# Electrical_Schematic_EasyEDA.net
KiCad netlist of a schematic drawn in EasyEDA
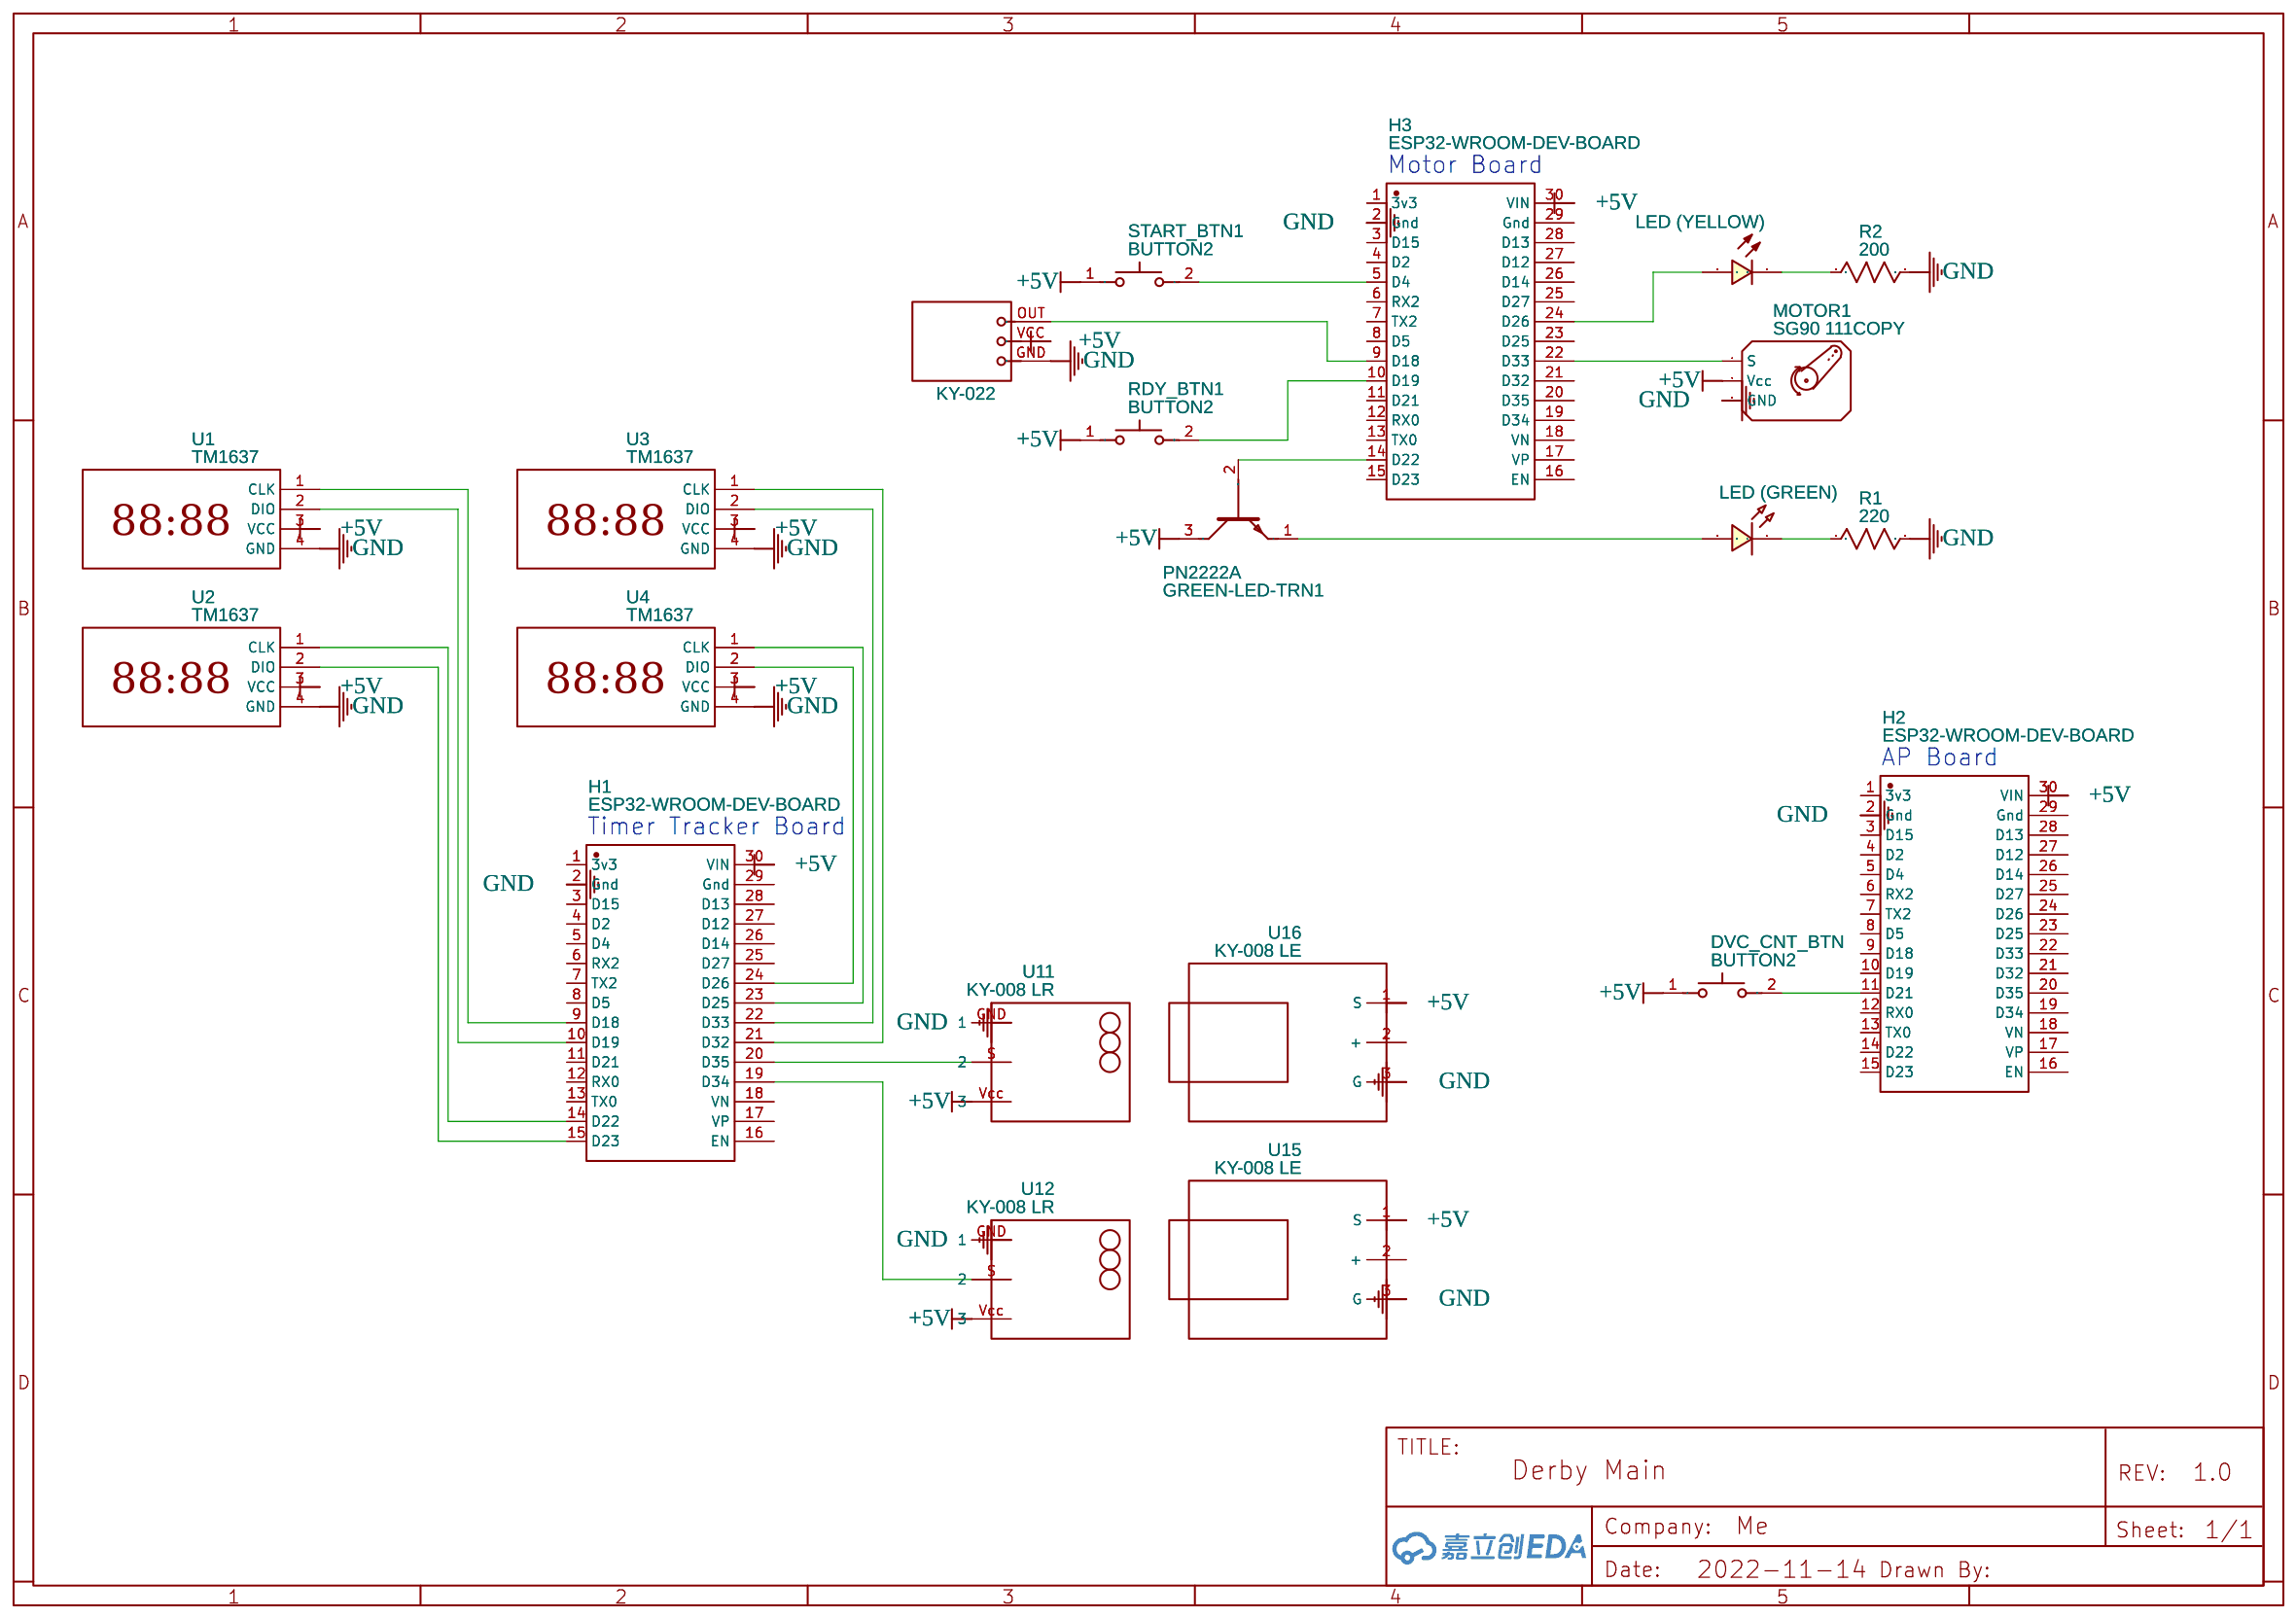
[diagram p0: schematic sheet]

(export (version "E")
  (design (tool "Eeschema 10.0.6"))
  (components
    (comp (ref "DVC_CNT_BTN")
      (value "BUTTON2")
      (fields (field (name "BOM_Supplier Part") "C9900005988"))
      (libsource (lib "") (part "BUTTON2_2"))
    )
    (comp (ref "GREEN-LED-TRN1") (value "PN2222A") (libsource (lib "") (part "PN2222A")))
    (comp (ref "H1")
      (value "ESP32-WROOM-DEV-BOARD")
      (fields
        (field (name "BOM_Manufacturer Part") "ESP32-WROOM-DEV")
        (field (name "BOM_Supplier Part") "ESP32")
      )
      (libsource (lib "") (part "ESP32-WROOM-DEV-BOARD"))
    )
    (comp (ref "H2")
      (value "ESP32-WROOM-DEV-BOARD")
      (fields
        (field (name "BOM_Manufacturer Part") "ESP32-WROOM-DEV")
        (field (name "BOM_Supplier Part") "ESP32")
      )
      (libsource (lib "") (part "ESP32-WROOM-DEV-BOARD"))
    )
    (comp (ref "H3")
      (value "ESP32-WROOM-DEV-BOARD")
      (fields
        (field (name "BOM_Manufacturer Part") "ESP32-WROOM-DEV")
        (field (name "BOM_Supplier Part") "ESP32")
      )
      (libsource (lib "") (part "ESP32-WROOM-DEV-BOARD"))
    )
    (comp (ref "LED1")
      (value "LED (GREEN)")
      (fields
        (field (name "BOM_Manufacturer Part") "LED三色(Red,Yellow,Green)")
        (field (name "BOM_Supplier Part") "C9900027004")
      )
      (libsource (lib "") (part "LED (GREEN)"))
    )
    (comp (ref "LED2")
      (value "LED (YELLOW)")
      (fields
        (field (name "BOM_Manufacturer Part") "19-213/Y2C-CQ1R1L/3T")
        (field (name "BOM_Supplier Part") "C264455")
      )
      (libsource (lib "") (part "Yellow LED"))
    )
    (comp (ref "MOTOR1") (value "SG90 111COPY") (libsource (lib "") (part "SG90 111COPY")))
    (comp (ref "R1") (value "220") (libsource (lib "") (part "R_AXIAL-0.6_US")))
    (comp (ref "R2") (value "200") (libsource (lib "") (part "R_AXIAL-0.6_US")))
    (comp (ref "RDY_BTN1")
      (value "BUTTON2")
      (fields (field (name "BOM_Supplier Part") "C9900005988"))
      (libsource (lib "") (part "BUTTON2"))
    )
    (comp (ref "START_BTN1")
      (value "BUTTON2")
      (fields (field (name "BOM_Supplier Part") "C9900005988"))
      (libsource (lib "") (part "BUTTON2_1"))
    )
    (comp (ref "U1") (value "TM1637") (libsource (lib "") (part "TM1637")))
    (comp (ref "U2") (value "TM1637") (libsource (lib "") (part "TM1637")))
    (comp (ref "U3") (value "TM1637") (libsource (lib "") (part "TM1637")))
    (comp (ref "U4") (value "TM1637") (libsource (lib "") (part "TM1637")))
    (comp (ref "U5") (value "KY-022") (libsource (lib "") (part "KY-022")))
    (comp (ref "U11")
      (value "KY-008 LR")
      (fields (field (name "BOM_Supplier Part") "KY-008"))
      (libsource (lib "") (part "Laser Receiver (KY-008)"))
    )
    (comp (ref "U12")
      (value "KY-008 LR")
      (fields (field (name "BOM_Supplier Part") "KY-008"))
      (libsource (lib "") (part "Laser Receiver (KY-008)"))
    )
    (comp (ref "U15") (value "KY-008 LE") (libsource (lib "") (part "KY-008//")))
    (comp (ref "U16") (value "KY-008 LE") (libsource (lib "") (part "KY-008//")))
  )
  (nets
    (net (code "1") (name "+5V") (class "Default")
      (node (ref "DVC_CNT_BTN") (pin "1") (pinfunction "1_1") (pintype "unspecified"))
      (node (ref "GREEN-LED-TRN1") (pin "3") (pinfunction "C_3") (pintype "bidirectional"))
      (node (ref "H1") (pin "30") (pinfunction "VIN_30") (pintype "unspecified"))
      (node (ref "H2") (pin "30") (pinfunction "VIN_30") (pintype "unspecified"))
      (node (ref "H3") (pin "30") (pinfunction "VIN_30") (pintype "unspecified"))
      (node (ref "MOTOR1") (pin "2") (pinfunction "Vcc_2") (pintype "unspecified"))
      (node (ref "RDY_BTN1") (pin "1") (pinfunction "1_1") (pintype "unspecified"))
      (node (ref "START_BTN1") (pin "1") (pinfunction "1_1") (pintype "unspecified"))
      (node (ref "U1") (pin "3") (pinfunction "VCC_3") (pintype "unspecified"))
      (node (ref "U15") (pin "1") (pinfunction "S_1") (pintype "unspecified"))
      (node (ref "U16") (pin "1") (pinfunction "S_1") (pintype "unspecified"))
      (node (ref "U2") (pin "3") (pinfunction "VCC_3") (pintype "unspecified"))
      (node (ref "U3") (pin "3") (pinfunction "VCC_3") (pintype "unspecified"))
      (node (ref "U4") (pin "3") (pinfunction "VCC_3") (pintype "unspecified"))
      (node (ref "U5") (pin "VCC") (pinfunction "2_VCC") (pintype "unspecified"))
    )
    (net (code "2") (name "GND") (class "Default")
      (node (ref "H1") (pin "2") (pinfunction "Gnd_2") (pintype "unspecified"))
      (node (ref "H2") (pin "2") (pinfunction "Gnd_2") (pintype "unspecified"))
      (node (ref "H3") (pin "2") (pinfunction "Gnd_2") (pintype "unspecified"))
      (node (ref "MOTOR1") (pin "3") (pinfunction "GND_3") (pintype "unspecified"))
      (node (ref "R1") (pin "2") (pinfunction "2_2") (pintype "unspecified"))
      (node (ref "R2") (pin "2") (pinfunction "2_2") (pintype "unspecified"))
      (node (ref "U1") (pin "4") (pinfunction "GND_4") (pintype "unspecified"))
      (node (ref "U11") (pin "GND") (pinfunction "1_GND") (pintype "unspecified"))
      (node (ref "U12") (pin "GND") (pinfunction "1_GND") (pintype "unspecified"))
      (node (ref "U15") (pin "3") (pinfunction "G_3") (pintype "unspecified"))
      (node (ref "U16") (pin "3") (pinfunction "G_3") (pintype "unspecified"))
      (node (ref "U2") (pin "4") (pinfunction "GND_4") (pintype "unspecified"))
      (node (ref "U3") (pin "4") (pinfunction "GND_4") (pintype "unspecified"))
      (node (ref "U4") (pin "4") (pinfunction "GND_4") (pintype "unspecified"))
      (node (ref "U5") (pin "GND") (pinfunction "1_GND") (pintype "unspecified"))
    )
    (net (code "3") (name "Net-(GREEN-LED-TRN1-B)") (class "Default")
      (node (ref "GREEN-LED-TRN1") (pin "2") (pinfunction "B_2") (pintype "bidirectional"))
      (node (ref "H3") (pin "14") (pinfunction "D22_14") (pintype "unspecified"))
    )
    (net (code "4") (name "Net-(GREEN-LED-TRN1-E)") (class "Default")
      (node (ref "GREEN-LED-TRN1") (pin "1") (pinfunction "E_1") (pintype "bidirectional"))
      (node (ref "LED1") (pin "2") (pinfunction "2_2") (pintype "unspecified"))
    )
    (net (code "5") (name "Net-(H1-D18)") (class "Default")
      (node (ref "H1") (pin "9") (pinfunction "D18_9") (pintype "unspecified"))
      (node (ref "U1") (pin "1") (pinfunction "CLK_1") (pintype "unspecified"))
    )
    (net (code "6") (name "Net-(H1-D19)") (class "Default")
      (node (ref "H1") (pin "10") (pinfunction "D19_10") (pintype "unspecified"))
      (node (ref "U1") (pin "2") (pinfunction "DIO_2") (pintype "unspecified"))
    )
    (net (code "7") (name "Net-(H1-D22)") (class "Default")
      (node (ref "H1") (pin "14") (pinfunction "D22_14") (pintype "unspecified"))
      (node (ref "U2") (pin "1") (pinfunction "CLK_1") (pintype "unspecified"))
    )
    (net (code "8") (name "Net-(H1-D23)") (class "Default")
      (node (ref "H1") (pin "15") (pinfunction "D23_15") (pintype "unspecified"))
      (node (ref "U2") (pin "2") (pinfunction "DIO_2") (pintype "unspecified"))
    )
    (net (code "9") (name "Net-(H1-D25)") (class "Default")
      (node (ref "H1") (pin "23") (pinfunction "D25_23") (pintype "unspecified"))
      (node (ref "U4") (pin "1") (pinfunction "CLK_1") (pintype "unspecified"))
    )
    (net (code "10") (name "Net-(H1-D26)") (class "Default")
      (node (ref "H1") (pin "24") (pinfunction "D26_24") (pintype "unspecified"))
      (node (ref "U4") (pin "2") (pinfunction "DIO_2") (pintype "unspecified"))
    )
    (net (code "11") (name "Net-(H1-D32)") (class "Default")
      (node (ref "H1") (pin "21") (pinfunction "D32_21") (pintype "unspecified"))
      (node (ref "U3") (pin "1") (pinfunction "CLK_1") (pintype "unspecified"))
    )
    (net (code "12") (name "Net-(H1-D33)") (class "Default")
      (node (ref "H1") (pin "22") (pinfunction "D33_22") (pintype "unspecified"))
      (node (ref "U3") (pin "2") (pinfunction "DIO_2") (pintype "unspecified"))
    )
    (net (code "13") (name "Net-(H1-D34)") (class "Default")
      (node (ref "H1") (pin "19") (pinfunction "D34_19") (pintype "unspecified"))
      (node (ref "U12") (pin "S") (pinfunction "2_S") (pintype "unspecified"))
    )
    (net (code "14") (name "Net-(H1-D35)") (class "Default")
      (node (ref "H1") (pin "20") (pinfunction "D35_20") (pintype "unspecified"))
      (node (ref "U11") (pin "S") (pinfunction "2_S") (pintype "unspecified"))
    )
    (net (code "15") (name "Net-(H2-D21)") (class "Default")
      (node (ref "DVC_CNT_BTN") (pin "2") (pinfunction "2_2") (pintype "unspecified"))
      (node (ref "H2") (pin "11") (pinfunction "D21_11") (pintype "unspecified"))
    )
    (net (code "16") (name "Net-(H3-D4)") (class "Default")
      (node (ref "H3") (pin "5") (pinfunction "D4_5") (pintype "unspecified"))
      (node (ref "START_BTN1") (pin "2") (pinfunction "2_2") (pintype "unspecified"))
    )
    (net (code "17") (name "Net-(H3-D18)") (class "Default")
      (node (ref "H3") (pin "9") (pinfunction "D18_9") (pintype "unspecified"))
      (node (ref "U5") (pin "OUT") (pinfunction "3_OUT") (pintype "unspecified"))
    )
    (net (code "18") (name "Net-(H3-D19)") (class "Default")
      (node (ref "H3") (pin "10") (pinfunction "D19_10") (pintype "unspecified"))
      (node (ref "RDY_BTN1") (pin "2") (pinfunction "2_2") (pintype "unspecified"))
    )
    (net (code "19") (name "Net-(H3-D26)") (class "Default")
      (node (ref "H3") (pin "24") (pinfunction "D26_24") (pintype "unspecified"))
      (node (ref "LED2") (pin "2") (pinfunction "A_2") (pintype "input"))
    )
    (net (code "20") (name "Net-(H3-D33)") (class "Default")
      (node (ref "H3") (pin "22") (pinfunction "D33_22") (pintype "unspecified"))
      (node (ref "MOTOR1") (pin "1") (pinfunction "S_1") (pintype "unspecified"))
    )
    (net (code "21") (name "Net-(LED1-Pad1)") (class "Default")
      (node (ref "LED1") (pin "1") (pinfunction "1_1") (pintype "unspecified"))
      (node (ref "R1") (pin "1") (pinfunction "1_1") (pintype "unspecified"))
    )
    (net (code "22") (name "Net-(LED2-C)") (class "Default")
      (node (ref "LED2") (pin "1") (pinfunction "C_1") (pintype "input"))
      (node (ref "R2") (pin "1") (pinfunction "1_1") (pintype "unspecified"))
    )
    (net (code "23") (name "unconnected-(H1-3v3-Pad1)") (class "Default")
      (node (ref "H1") (pin "1") (pinfunction "3v3_1") (pintype "unspecified"))
    )
    (net (code "24") (name "unconnected-(H1-D2-Pad4)") (class "Default")
      (node (ref "H1") (pin "4") (pinfunction "D2_4") (pintype "unspecified"))
    )
    (net (code "25") (name "unconnected-(H1-D4-Pad5)") (class "Default")
      (node (ref "H1") (pin "5") (pinfunction "D4_5") (pintype "unspecified"))
    )
    (net (code "26") (name "unconnected-(H1-D5-Pad8)") (class "Default")
      (node (ref "H1") (pin "8") (pinfunction "D5_8") (pintype "unspecified"))
    )
    (net (code "27") (name "unconnected-(H1-D12-Pad27)") (class "Default")
      (node (ref "H1") (pin "27") (pinfunction "D12_27") (pintype "unspecified"))
    )
    (net (code "28") (name "unconnected-(H1-D13-Pad28)") (class "Default")
      (node (ref "H1") (pin "28") (pinfunction "D13_28") (pintype "unspecified"))
    )
    (net (code "29") (name "unconnected-(H1-D14-Pad26)") (class "Default")
      (node (ref "H1") (pin "26") (pinfunction "D14_26") (pintype "unspecified"))
    )
    (net (code "30") (name "unconnected-(H1-D15-Pad3)") (class "Default")
      (node (ref "H1") (pin "3") (pinfunction "D15_3") (pintype "unspecified"))
    )
    (net (code "31") (name "unconnected-(H1-D21-Pad11)") (class "Default")
      (node (ref "H1") (pin "11") (pinfunction "D21_11") (pintype "unspecified"))
    )
    (net (code "32") (name "unconnected-(H1-D27-Pad25)") (class "Default")
      (node (ref "H1") (pin "25") (pinfunction "D27_25") (pintype "unspecified"))
    )
    (net (code "33") (name "unconnected-(H1-EN-Pad16)") (class "Default")
      (node (ref "H1") (pin "16") (pinfunction "EN_16") (pintype "unspecified"))
    )
    (net (code "34") (name "unconnected-(H1-Gnd-Pad29)") (class "Default")
      (node (ref "H1") (pin "29") (pinfunction "Gnd_29") (pintype "unspecified"))
    )
    (net (code "35") (name "unconnected-(H1-RX0-Pad12)") (class "Default")
      (node (ref "H1") (pin "12") (pinfunction "RX0_12") (pintype "unspecified"))
    )
    (net (code "36") (name "unconnected-(H1-RX2-Pad6)") (class "Default")
      (node (ref "H1") (pin "6") (pinfunction "RX2_6") (pintype "unspecified"))
    )
    (net (code "37") (name "unconnected-(H1-TX0-Pad13)") (class "Default")
      (node (ref "H1") (pin "13") (pinfunction "TX0_13") (pintype "unspecified"))
    )
    (net (code "38") (name "unconnected-(H1-TX2-Pad7)") (class "Default")
      (node (ref "H1") (pin "7") (pinfunction "TX2_7") (pintype "unspecified"))
    )
    (net (code "39") (name "unconnected-(H1-VN-Pad18)") (class "Default")
      (node (ref "H1") (pin "18") (pinfunction "VN_18") (pintype "unspecified"))
    )
    (net (code "40") (name "unconnected-(H1-VP-Pad17)") (class "Default")
      (node (ref "H1") (pin "17") (pinfunction "VP_17") (pintype "unspecified"))
    )
    (net (code "41") (name "unconnected-(H2-3v3-Pad1)") (class "Default")
      (node (ref "H2") (pin "1") (pinfunction "3v3_1") (pintype "unspecified"))
    )
    (net (code "42") (name "unconnected-(H2-D2-Pad4)") (class "Default")
      (node (ref "H2") (pin "4") (pinfunction "D2_4") (pintype "unspecified"))
    )
    (net (code "43") (name "unconnected-(H2-D4-Pad5)") (class "Default")
      (node (ref "H2") (pin "5") (pinfunction "D4_5") (pintype "unspecified"))
    )
    (net (code "44") (name "unconnected-(H2-D5-Pad8)") (class "Default")
      (node (ref "H2") (pin "8") (pinfunction "D5_8") (pintype "unspecified"))
    )
    (net (code "45") (name "unconnected-(H2-D12-Pad27)") (class "Default")
      (node (ref "H2") (pin "27") (pinfunction "D12_27") (pintype "unspecified"))
    )
    (net (code "46") (name "unconnected-(H2-D13-Pad28)") (class "Default")
      (node (ref "H2") (pin "28") (pinfunction "D13_28") (pintype "unspecified"))
    )
    (net (code "47") (name "unconnected-(H2-D14-Pad26)") (class "Default")
      (node (ref "H2") (pin "26") (pinfunction "D14_26") (pintype "unspecified"))
    )
    (net (code "48") (name "unconnected-(H2-D15-Pad3)") (class "Default")
      (node (ref "H2") (pin "3") (pinfunction "D15_3") (pintype "unspecified"))
    )
    (net (code "49") (name "unconnected-(H2-D18-Pad9)") (class "Default")
      (node (ref "H2") (pin "9") (pinfunction "D18_9") (pintype "unspecified"))
    )
    (net (code "50") (name "unconnected-(H2-D19-Pad10)") (class "Default")
      (node (ref "H2") (pin "10") (pinfunction "D19_10") (pintype "unspecified"))
    )
    (net (code "51") (name "unconnected-(H2-D22-Pad14)") (class "Default")
      (node (ref "H2") (pin "14") (pinfunction "D22_14") (pintype "unspecified"))
    )
    (net (code "52") (name "unconnected-(H2-D23-Pad15)") (class "Default")
      (node (ref "H2") (pin "15") (pinfunction "D23_15") (pintype "unspecified"))
    )
    (net (code "53") (name "unconnected-(H2-D25-Pad23)") (class "Default")
      (node (ref "H2") (pin "23") (pinfunction "D25_23") (pintype "unspecified"))
    )
    (net (code "54") (name "unconnected-(H2-D26-Pad24)") (class "Default")
      (node (ref "H2") (pin "24") (pinfunction "D26_24") (pintype "unspecified"))
    )
    (net (code "55") (name "unconnected-(H2-D27-Pad25)") (class "Default")
      (node (ref "H2") (pin "25") (pinfunction "D27_25") (pintype "unspecified"))
    )
    (net (code "56") (name "unconnected-(H2-D32-Pad21)") (class "Default")
      (node (ref "H2") (pin "21") (pinfunction "D32_21") (pintype "unspecified"))
    )
    (net (code "57") (name "unconnected-(H2-D33-Pad22)") (class "Default")
      (node (ref "H2") (pin "22") (pinfunction "D33_22") (pintype "unspecified"))
    )
    (net (code "58") (name "unconnected-(H2-D34-Pad19)") (class "Default")
      (node (ref "H2") (pin "19") (pinfunction "D34_19") (pintype "unspecified"))
    )
    (net (code "59") (name "unconnected-(H2-D35-Pad20)") (class "Default")
      (node (ref "H2") (pin "20") (pinfunction "D35_20") (pintype "unspecified"))
    )
    (net (code "60") (name "unconnected-(H2-EN-Pad16)") (class "Default")
      (node (ref "H2") (pin "16") (pinfunction "EN_16") (pintype "unspecified"))
    )
    (net (code "61") (name "unconnected-(H2-Gnd-Pad29)") (class "Default")
      (node (ref "H2") (pin "29") (pinfunction "Gnd_29") (pintype "unspecified"))
    )
    (net (code "62") (name "unconnected-(H2-RX0-Pad12)") (class "Default")
      (node (ref "H2") (pin "12") (pinfunction "RX0_12") (pintype "unspecified"))
    )
    (net (code "63") (name "unconnected-(H2-RX2-Pad6)") (class "Default")
      (node (ref "H2") (pin "6") (pinfunction "RX2_6") (pintype "unspecified"))
    )
    (net (code "64") (name "unconnected-(H2-TX0-Pad13)") (class "Default")
      (node (ref "H2") (pin "13") (pinfunction "TX0_13") (pintype "unspecified"))
    )
    (net (code "65") (name "unconnected-(H2-TX2-Pad7)") (class "Default")
      (node (ref "H2") (pin "7") (pinfunction "TX2_7") (pintype "unspecified"))
    )
    (net (code "66") (name "unconnected-(H2-VN-Pad18)") (class "Default")
      (node (ref "H2") (pin "18") (pinfunction "VN_18") (pintype "unspecified"))
    )
    (net (code "67") (name "unconnected-(H2-VP-Pad17)") (class "Default")
      (node (ref "H2") (pin "17") (pinfunction "VP_17") (pintype "unspecified"))
    )
    (net (code "68") (name "unconnected-(H3-3v3-Pad1)") (class "Default")
      (node (ref "H3") (pin "1") (pinfunction "3v3_1") (pintype "unspecified"))
    )
    (net (code "69") (name "unconnected-(H3-D2-Pad4)") (class "Default")
      (node (ref "H3") (pin "4") (pinfunction "D2_4") (pintype "unspecified"))
    )
    (net (code "70") (name "unconnected-(H3-D5-Pad8)") (class "Default")
      (node (ref "H3") (pin "8") (pinfunction "D5_8") (pintype "unspecified"))
    )
    (net (code "71") (name "unconnected-(H3-D12-Pad27)") (class "Default")
      (node (ref "H3") (pin "27") (pinfunction "D12_27") (pintype "unspecified"))
    )
    (net (code "72") (name "unconnected-(H3-D13-Pad28)") (class "Default")
      (node (ref "H3") (pin "28") (pinfunction "D13_28") (pintype "unspecified"))
    )
    (net (code "73") (name "unconnected-(H3-D14-Pad26)") (class "Default")
      (node (ref "H3") (pin "26") (pinfunction "D14_26") (pintype "unspecified"))
    )
    (net (code "74") (name "unconnected-(H3-D15-Pad3)") (class "Default")
      (node (ref "H3") (pin "3") (pinfunction "D15_3") (pintype "unspecified"))
    )
    (net (code "75") (name "unconnected-(H3-D21-Pad11)") (class "Default")
      (node (ref "H3") (pin "11") (pinfunction "D21_11") (pintype "unspecified"))
    )
    (net (code "76") (name "unconnected-(H3-D23-Pad15)") (class "Default")
      (node (ref "H3") (pin "15") (pinfunction "D23_15") (pintype "unspecified"))
    )
    (net (code "77") (name "unconnected-(H3-D25-Pad23)") (class "Default")
      (node (ref "H3") (pin "23") (pinfunction "D25_23") (pintype "unspecified"))
    )
    (net (code "78") (name "unconnected-(H3-D27-Pad25)") (class "Default")
      (node (ref "H3") (pin "25") (pinfunction "D27_25") (pintype "unspecified"))
    )
    (net (code "79") (name "unconnected-(H3-D32-Pad21)") (class "Default")
      (node (ref "H3") (pin "21") (pinfunction "D32_21") (pintype "unspecified"))
    )
    (net (code "80") (name "unconnected-(H3-D34-Pad19)") (class "Default")
      (node (ref "H3") (pin "19") (pinfunction "D34_19") (pintype "unspecified"))
    )
    (net (code "81") (name "unconnected-(H3-D35-Pad20)") (class "Default")
      (node (ref "H3") (pin "20") (pinfunction "D35_20") (pintype "unspecified"))
    )
    (net (code "82") (name "unconnected-(H3-EN-Pad16)") (class "Default")
      (node (ref "H3") (pin "16") (pinfunction "EN_16") (pintype "unspecified"))
    )
    (net (code "83") (name "unconnected-(H3-Gnd-Pad29)") (class "Default")
      (node (ref "H3") (pin "29") (pinfunction "Gnd_29") (pintype "unspecified"))
    )
    (net (code "84") (name "unconnected-(H3-RX0-Pad12)") (class "Default")
      (node (ref "H3") (pin "12") (pinfunction "RX0_12") (pintype "unspecified"))
    )
    (net (code "85") (name "unconnected-(H3-RX2-Pad6)") (class "Default")
      (node (ref "H3") (pin "6") (pinfunction "RX2_6") (pintype "unspecified"))
    )
    (net (code "86") (name "unconnected-(H3-TX0-Pad13)") (class "Default")
      (node (ref "H3") (pin "13") (pinfunction "TX0_13") (pintype "unspecified"))
    )
    (net (code "87") (name "unconnected-(H3-TX2-Pad7)") (class "Default")
      (node (ref "H3") (pin "7") (pinfunction "TX2_7") (pintype "unspecified"))
    )
    (net (code "88") (name "unconnected-(H3-VN-Pad18)") (class "Default")
      (node (ref "H3") (pin "18") (pinfunction "VN_18") (pintype "unspecified"))
    )
    (net (code "89") (name "unconnected-(H3-VP-Pad17)") (class "Default")
      (node (ref "H3") (pin "17") (pinfunction "VP_17") (pintype "unspecified"))
    )
    (net (code "90") (name "unconnected-(U11-3-PadVcc)") (class "Default")
      (node (ref "U11") (pin "Vcc") (pinfunction "3_Vcc") (pintype "unspecified"))
    )
    (net (code "91") (name "unconnected-(U12-3-PadVcc)") (class "Default")
      (node (ref "U12") (pin "Vcc") (pinfunction "3_Vcc") (pintype "unspecified"))
    )
    (net (code "92") (name "unconnected-(U15-+-Pad2)") (class "Default")
      (node (ref "U15") (pin "2") (pinfunction "+_2") (pintype "unspecified"))
    )
    (net (code "93") (name "unconnected-(U16-+-Pad2)") (class "Default")
      (node (ref "U16") (pin "2") (pinfunction "+_2") (pintype "unspecified"))
    )
  )
)
